# PowerGnd.net
KiCad netlist of a schematic drawn in Altium Designer
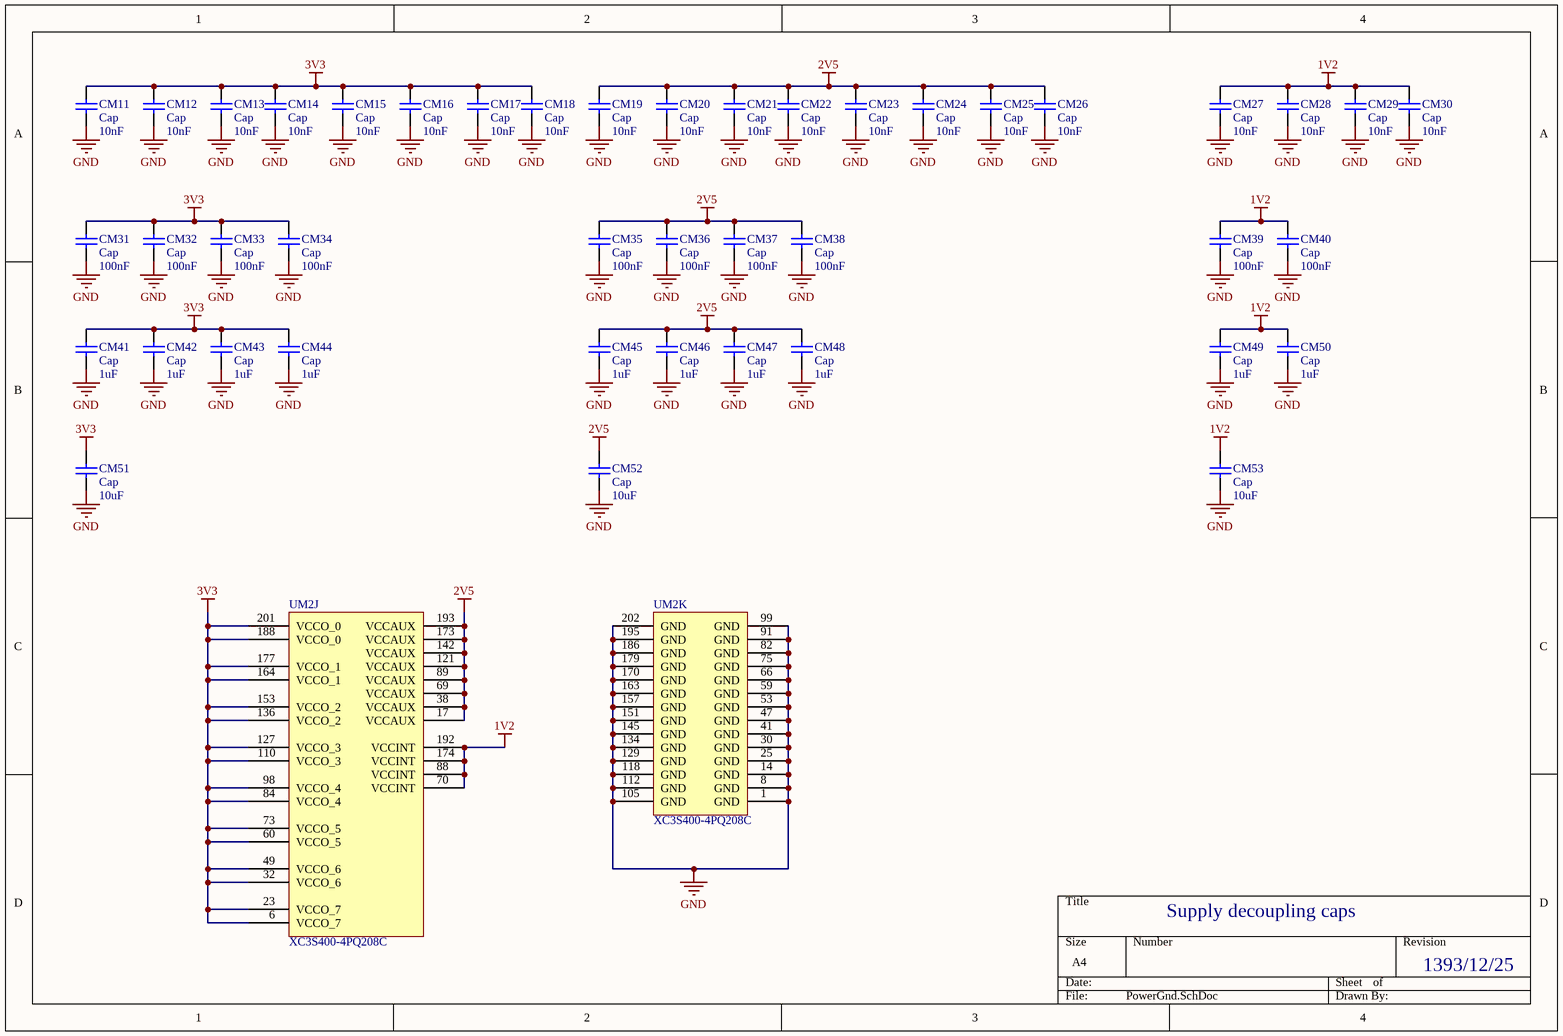
[diagram p0: PowerGnd.SchDoc]

(export (version "E")
  (design (tool "Eeschema 10.0.6"))
  (components
    (comp (ref "CM11")
      (value "Cap")
      (footprint "C0805")
      (description "Capacitor")
      (fields (field (name "ALTIUM_VALUE") "10nF") (field (name "PUBLISHER") "Altium Limited"))
      (libsource (lib "Miscellaneous Devices") (part "Cap"))
    )
    (comp (ref "CM12")
      (value "Cap")
      (footprint "C0805")
      (description "Capacitor")
      (fields (field (name "ALTIUM_VALUE") "10nF") (field (name "PUBLISHER") "Altium Limited"))
      (libsource (lib "Miscellaneous Devices") (part "Cap"))
    )
    (comp (ref "CM13")
      (value "Cap")
      (footprint "C0805")
      (description "Capacitor")
      (fields (field (name "ALTIUM_VALUE") "10nF") (field (name "PUBLISHER") "Altium Limited"))
      (libsource (lib "Miscellaneous Devices") (part "Cap"))
    )
    (comp (ref "CM14")
      (value "Cap")
      (footprint "C0805")
      (description "Capacitor")
      (fields (field (name "ALTIUM_VALUE") "10nF") (field (name "PUBLISHER") "Altium Limited"))
      (libsource (lib "Miscellaneous Devices") (part "Cap"))
    )
    (comp (ref "CM15")
      (value "Cap")
      (footprint "C0805")
      (description "Capacitor")
      (fields (field (name "ALTIUM_VALUE") "10nF") (field (name "PUBLISHER") "Altium Limited"))
      (libsource (lib "Miscellaneous Devices") (part "Cap"))
    )
    (comp (ref "CM16")
      (value "Cap")
      (footprint "C0805")
      (description "Capacitor")
      (fields (field (name "ALTIUM_VALUE") "10nF") (field (name "PUBLISHER") "Altium Limited"))
      (libsource (lib "Miscellaneous Devices") (part "Cap"))
    )
    (comp (ref "CM17")
      (value "Cap")
      (footprint "C0805")
      (description "Capacitor")
      (fields (field (name "ALTIUM_VALUE") "10nF") (field (name "PUBLISHER") "Altium Limited"))
      (libsource (lib "Miscellaneous Devices") (part "Cap"))
    )
    (comp (ref "CM18")
      (value "Cap")
      (footprint "C0805")
      (description "Capacitor")
      (fields (field (name "ALTIUM_VALUE") "10nF") (field (name "PUBLISHER") "Altium Limited"))
      (libsource (lib "Miscellaneous Devices") (part "Cap"))
    )
    (comp (ref "CM19")
      (value "Cap")
      (footprint "C0805")
      (description "Capacitor")
      (fields (field (name "ALTIUM_VALUE") "10nF") (field (name "PUBLISHER") "Altium Limited"))
      (libsource (lib "Miscellaneous Devices") (part "Cap"))
    )
    (comp (ref "CM20")
      (value "Cap")
      (footprint "C0805")
      (description "Capacitor")
      (fields (field (name "ALTIUM_VALUE") "10nF") (field (name "PUBLISHER") "Altium Limited"))
      (libsource (lib "Miscellaneous Devices") (part "Cap"))
    )
    (comp (ref "CM21")
      (value "Cap")
      (footprint "C0805")
      (description "Capacitor")
      (fields (field (name "ALTIUM_VALUE") "10nF") (field (name "PUBLISHER") "Altium Limited"))
      (libsource (lib "Miscellaneous Devices") (part "Cap"))
    )
    (comp (ref "CM22")
      (value "Cap")
      (footprint "C0805")
      (description "Capacitor")
      (fields (field (name "ALTIUM_VALUE") "10nF") (field (name "PUBLISHER") "Altium Limited"))
      (libsource (lib "Miscellaneous Devices") (part "Cap"))
    )
    (comp (ref "CM23")
      (value "Cap")
      (footprint "C0805")
      (description "Capacitor")
      (fields (field (name "ALTIUM_VALUE") "10nF") (field (name "PUBLISHER") "Altium Limited"))
      (libsource (lib "Miscellaneous Devices") (part "Cap"))
    )
    (comp (ref "CM24")
      (value "Cap")
      (footprint "C0805")
      (description "Capacitor")
      (fields (field (name "ALTIUM_VALUE") "10nF") (field (name "PUBLISHER") "Altium Limited"))
      (libsource (lib "Miscellaneous Devices") (part "Cap"))
    )
    (comp (ref "CM25")
      (value "Cap")
      (footprint "C0805")
      (description "Capacitor")
      (fields (field (name "ALTIUM_VALUE") "10nF") (field (name "PUBLISHER") "Altium Limited"))
      (libsource (lib "Miscellaneous Devices") (part "Cap"))
    )
    (comp (ref "CM26")
      (value "Cap")
      (footprint "C0805")
      (description "Capacitor")
      (fields (field (name "ALTIUM_VALUE") "10nF") (field (name "PUBLISHER") "Altium Limited"))
      (libsource (lib "Miscellaneous Devices") (part "Cap"))
    )
    (comp (ref "CM27")
      (value "Cap")
      (footprint "C0805")
      (description "Capacitor")
      (fields (field (name "ALTIUM_VALUE") "10nF") (field (name "PUBLISHER") "Altium Limited"))
      (libsource (lib "Miscellaneous Devices") (part "Cap"))
    )
    (comp (ref "CM28")
      (value "Cap")
      (footprint "C0805")
      (description "Capacitor")
      (fields (field (name "ALTIUM_VALUE") "10nF") (field (name "PUBLISHER") "Altium Limited"))
      (libsource (lib "Miscellaneous Devices") (part "Cap"))
    )
    (comp (ref "CM29")
      (value "Cap")
      (footprint "C0805")
      (description "Capacitor")
      (fields (field (name "ALTIUM_VALUE") "10nF") (field (name "PUBLISHER") "Altium Limited"))
      (libsource (lib "Miscellaneous Devices") (part "Cap"))
    )
    (comp (ref "CM30")
      (value "Cap")
      (footprint "C0805")
      (description "Capacitor")
      (fields (field (name "ALTIUM_VALUE") "10nF") (field (name "PUBLISHER") "Altium Limited"))
      (libsource (lib "Miscellaneous Devices") (part "Cap"))
    )
    (comp (ref "CM31")
      (value "Cap")
      (footprint "C0805")
      (description "Capacitor")
      (fields (field (name "ALTIUM_VALUE") "100nF") (field (name "PUBLISHER") "Altium Limited"))
      (libsource (lib "Miscellaneous Devices") (part "Cap"))
    )
    (comp (ref "CM32")
      (value "Cap")
      (footprint "C0805")
      (description "Capacitor")
      (fields (field (name "ALTIUM_VALUE") "100nF") (field (name "PUBLISHER") "Altium Limited"))
      (libsource (lib "Miscellaneous Devices") (part "Cap"))
    )
    (comp (ref "CM33")
      (value "Cap")
      (footprint "C0805")
      (description "Capacitor")
      (fields (field (name "ALTIUM_VALUE") "100nF") (field (name "PUBLISHER") "Altium Limited"))
      (libsource (lib "Miscellaneous Devices") (part "Cap"))
    )
    (comp (ref "CM34")
      (value "Cap")
      (footprint "C0805")
      (description "Capacitor")
      (fields (field (name "ALTIUM_VALUE") "100nF") (field (name "PUBLISHER") "Altium Limited"))
      (libsource (lib "Miscellaneous Devices") (part "Cap"))
    )
    (comp (ref "CM35")
      (value "Cap")
      (footprint "C0805")
      (description "Capacitor")
      (fields (field (name "ALTIUM_VALUE") "100nF") (field (name "PUBLISHER") "Altium Limited"))
      (libsource (lib "Miscellaneous Devices") (part "Cap"))
    )
    (comp (ref "CM36")
      (value "Cap")
      (footprint "C0805")
      (description "Capacitor")
      (fields (field (name "ALTIUM_VALUE") "100nF") (field (name "PUBLISHER") "Altium Limited"))
      (libsource (lib "Miscellaneous Devices") (part "Cap"))
    )
    (comp (ref "CM37")
      (value "Cap")
      (footprint "C0805")
      (description "Capacitor")
      (fields (field (name "ALTIUM_VALUE") "100nF") (field (name "PUBLISHER") "Altium Limited"))
      (libsource (lib "Miscellaneous Devices") (part "Cap"))
    )
    (comp (ref "CM38")
      (value "Cap")
      (footprint "C0805")
      (description "Capacitor")
      (fields (field (name "ALTIUM_VALUE") "100nF") (field (name "PUBLISHER") "Altium Limited"))
      (libsource (lib "Miscellaneous Devices") (part "Cap"))
    )
    (comp (ref "CM39")
      (value "Cap")
      (footprint "C0805")
      (description "Capacitor")
      (fields (field (name "ALTIUM_VALUE") "100nF") (field (name "PUBLISHER") "Altium Limited"))
      (libsource (lib "Miscellaneous Devices") (part "Cap"))
    )
    (comp (ref "CM40")
      (value "Cap")
      (footprint "C0805")
      (description "Capacitor")
      (fields (field (name "ALTIUM_VALUE") "100nF") (field (name "PUBLISHER") "Altium Limited"))
      (libsource (lib "Miscellaneous Devices") (part "Cap"))
    )
    (comp (ref "CM41")
      (value "Cap")
      (footprint "C0805")
      (description "Capacitor")
      (fields (field (name "ALTIUM_VALUE") "1uF") (field (name "PUBLISHER") "Altium Limited"))
      (libsource (lib "Miscellaneous Devices") (part "Cap"))
    )
    (comp (ref "CM42")
      (value "Cap")
      (footprint "C0805")
      (description "Capacitor")
      (fields (field (name "ALTIUM_VALUE") "1uF") (field (name "PUBLISHER") "Altium Limited"))
      (libsource (lib "Miscellaneous Devices") (part "Cap"))
    )
    (comp (ref "CM43")
      (value "Cap")
      (footprint "C0805")
      (description "Capacitor")
      (fields (field (name "ALTIUM_VALUE") "1uF") (field (name "PUBLISHER") "Altium Limited"))
      (libsource (lib "Miscellaneous Devices") (part "Cap"))
    )
    (comp (ref "CM44")
      (value "Cap")
      (footprint "C0805")
      (description "Capacitor")
      (fields (field (name "ALTIUM_VALUE") "1uF") (field (name "PUBLISHER") "Altium Limited"))
      (libsource (lib "Miscellaneous Devices") (part "Cap"))
    )
    (comp (ref "CM45")
      (value "Cap")
      (footprint "C0805")
      (description "Capacitor")
      (fields (field (name "ALTIUM_VALUE") "1uF") (field (name "PUBLISHER") "Altium Limited"))
      (libsource (lib "Miscellaneous Devices") (part "Cap"))
    )
    (comp (ref "CM46")
      (value "Cap")
      (footprint "C0805")
      (description "Capacitor")
      (fields (field (name "ALTIUM_VALUE") "1uF") (field (name "PUBLISHER") "Altium Limited"))
      (libsource (lib "Miscellaneous Devices") (part "Cap"))
    )
    (comp (ref "CM47")
      (value "Cap")
      (footprint "C0805")
      (description "Capacitor")
      (fields (field (name "ALTIUM_VALUE") "1uF") (field (name "PUBLISHER") "Altium Limited"))
      (libsource (lib "Miscellaneous Devices") (part "Cap"))
    )
    (comp (ref "CM48")
      (value "Cap")
      (footprint "C0805")
      (description "Capacitor")
      (fields (field (name "ALTIUM_VALUE") "1uF") (field (name "PUBLISHER") "Altium Limited"))
      (libsource (lib "Miscellaneous Devices") (part "Cap"))
    )
    (comp (ref "CM49")
      (value "Cap")
      (footprint "C0805")
      (description "Capacitor")
      (fields (field (name "ALTIUM_VALUE") "1uF") (field (name "PUBLISHER") "Altium Limited"))
      (libsource (lib "Miscellaneous Devices") (part "Cap"))
    )
    (comp (ref "CM50")
      (value "Cap")
      (footprint "C0805")
      (description "Capacitor")
      (fields (field (name "ALTIUM_VALUE") "1uF") (field (name "PUBLISHER") "Altium Limited"))
      (libsource (lib "Miscellaneous Devices") (part "Cap"))
    )
    (comp (ref "CM51")
      (value "Cap")
      (footprint "C0805")
      (description "Capacitor")
      (fields (field (name "ALTIUM_VALUE") "10uF") (field (name "PUBLISHER") "Altium Limited"))
      (libsource (lib "Miscellaneous Devices") (part "Cap"))
    )
    (comp (ref "CM52")
      (value "Cap")
      (footprint "C0805")
      (description "Capacitor")
      (fields (field (name "ALTIUM_VALUE") "10uF") (field (name "PUBLISHER") "Altium Limited"))
      (libsource (lib "Miscellaneous Devices") (part "Cap"))
    )
    (comp (ref "CM53")
      (value "Cap")
      (footprint "C0805")
      (description "Capacitor")
      (fields (field (name "ALTIUM_VALUE") "10uF") (field (name "PUBLISHER") "Altium Limited"))
      (libsource (lib "Miscellaneous Devices") (part "Cap"))
    )
    (comp (ref "UM2")
      (value "XC3S400-4PQ208C")
      (footprint "PQ208_N")
      (description "Spartan-3 1.2V FPGA, 141 User I/Os, 208-Pin PQFP, Standard Performance, Commercial Grade")
      (fields (field (name "PUBLISHER") "Altium Limited"))
      (libsource (lib "Xilinx Spartan-3") (part "XC3S400-4PQ208C"))
    )
  )
  (nets
    (net (code "1") (name "1V2") (class "Default")
      (node (ref "CM27") (pin "2") (pinfunction "2_2") (pintype "passive"))
      (node (ref "CM28") (pin "2") (pinfunction "2_2") (pintype "passive"))
      (node (ref "CM29") (pin "2") (pinfunction "2_2") (pintype "passive"))
      (node (ref "CM30") (pin "2") (pinfunction "2_2") (pintype "passive"))
      (node (ref "CM39") (pin "2") (pinfunction "2_2") (pintype "passive"))
      (node (ref "CM40") (pin "2") (pinfunction "2_2") (pintype "passive"))
      (node (ref "CM49") (pin "2") (pinfunction "2_2") (pintype "passive"))
      (node (ref "CM50") (pin "2") (pinfunction "2_2") (pintype "passive"))
      (node (ref "CM53") (pin "2") (pinfunction "2_2") (pintype "passive"))
      (node (ref "UM2") (pin "174") (pinfunction "VCCINT_174") (pintype "power_in"))
      (node (ref "UM2") (pin "192") (pinfunction "VCCINT_192") (pintype "power_in"))
      (node (ref "UM2") (pin "70") (pinfunction "VCCINT_70") (pintype "power_in"))
      (node (ref "UM2") (pin "88") (pinfunction "VCCINT_88") (pintype "power_in"))
    )
    (net (code "2") (name "2V5") (class "Default")
      (node (ref "CM19") (pin "2") (pinfunction "2_2") (pintype "passive"))
      (node (ref "CM20") (pin "2") (pinfunction "2_2") (pintype "passive"))
      (node (ref "CM21") (pin "2") (pinfunction "2_2") (pintype "passive"))
      (node (ref "CM22") (pin "2") (pinfunction "2_2") (pintype "passive"))
      (node (ref "CM23") (pin "2") (pinfunction "2_2") (pintype "passive"))
      (node (ref "CM24") (pin "2") (pinfunction "2_2") (pintype "passive"))
      (node (ref "CM25") (pin "2") (pinfunction "2_2") (pintype "passive"))
      (node (ref "CM26") (pin "2") (pinfunction "2_2") (pintype "passive"))
      (node (ref "CM35") (pin "2") (pinfunction "2_2") (pintype "passive"))
      (node (ref "CM36") (pin "2") (pinfunction "2_2") (pintype "passive"))
      (node (ref "CM37") (pin "2") (pinfunction "2_2") (pintype "passive"))
      (node (ref "CM38") (pin "2") (pinfunction "2_2") (pintype "passive"))
      (node (ref "CM45") (pin "2") (pinfunction "2_2") (pintype "passive"))
      (node (ref "CM46") (pin "2") (pinfunction "2_2") (pintype "passive"))
      (node (ref "CM47") (pin "2") (pinfunction "2_2") (pintype "passive"))
      (node (ref "CM48") (pin "2") (pinfunction "2_2") (pintype "passive"))
      (node (ref "CM52") (pin "2") (pinfunction "2_2") (pintype "passive"))
      (node (ref "UM2") (pin "121") (pinfunction "VCCAUX_121") (pintype "power_in"))
      (node (ref "UM2") (pin "142") (pinfunction "VCCAUX_142") (pintype "power_in"))
      (node (ref "UM2") (pin "17") (pinfunction "VCCAUX_17") (pintype "power_in"))
      (node (ref "UM2") (pin "173") (pinfunction "VCCAUX_173") (pintype "power_in"))
      (node (ref "UM2") (pin "193") (pinfunction "VCCAUX_193") (pintype "power_in"))
      (node (ref "UM2") (pin "38") (pinfunction "VCCAUX_38") (pintype "power_in"))
      (node (ref "UM2") (pin "69") (pinfunction "VCCAUX_69") (pintype "power_in"))
      (node (ref "UM2") (pin "89") (pinfunction "VCCAUX_89") (pintype "power_in"))
    )
    (net (code "3") (name "3V3") (class "Default")
      (node (ref "CM11") (pin "2") (pinfunction "2_2") (pintype "passive"))
      (node (ref "CM12") (pin "2") (pinfunction "2_2") (pintype "passive"))
      (node (ref "CM13") (pin "2") (pinfunction "2_2") (pintype "passive"))
      (node (ref "CM14") (pin "2") (pinfunction "2_2") (pintype "passive"))
      (node (ref "CM15") (pin "2") (pinfunction "2_2") (pintype "passive"))
      (node (ref "CM16") (pin "2") (pinfunction "2_2") (pintype "passive"))
      (node (ref "CM17") (pin "2") (pinfunction "2_2") (pintype "passive"))
      (node (ref "CM18") (pin "2") (pinfunction "2_2") (pintype "passive"))
      (node (ref "CM31") (pin "2") (pinfunction "2_2") (pintype "passive"))
      (node (ref "CM32") (pin "2") (pinfunction "2_2") (pintype "passive"))
      (node (ref "CM33") (pin "2") (pinfunction "2_2") (pintype "passive"))
      (node (ref "CM34") (pin "2") (pinfunction "2_2") (pintype "passive"))
      (node (ref "CM41") (pin "2") (pinfunction "2_2") (pintype "passive"))
      (node (ref "CM42") (pin "2") (pinfunction "2_2") (pintype "passive"))
      (node (ref "CM43") (pin "2") (pinfunction "2_2") (pintype "passive"))
      (node (ref "CM44") (pin "2") (pinfunction "2_2") (pintype "passive"))
      (node (ref "CM51") (pin "2") (pinfunction "2_2") (pintype "passive"))
      (node (ref "UM2") (pin "110") (pinfunction "VCCO_3_110") (pintype "power_in"))
      (node (ref "UM2") (pin "127") (pinfunction "VCCO_3_127") (pintype "power_in"))
      (node (ref "UM2") (pin "136") (pinfunction "VCCO_2_136") (pintype "power_in"))
      (node (ref "UM2") (pin "153") (pinfunction "VCCO_2_153") (pintype "power_in"))
      (node (ref "UM2") (pin "164") (pinfunction "VCCO_1_164") (pintype "power_in"))
      (node (ref "UM2") (pin "177") (pinfunction "VCCO_1_177") (pintype "power_in"))
      (node (ref "UM2") (pin "188") (pinfunction "VCCO_0_188") (pintype "power_in"))
      (node (ref "UM2") (pin "201") (pinfunction "VCCO_0_201") (pintype "power_in"))
      (node (ref "UM2") (pin "23") (pinfunction "VCCO_7_23") (pintype "power_in"))
      (node (ref "UM2") (pin "32") (pinfunction "VCCO_6_32") (pintype "power_in"))
      (node (ref "UM2") (pin "49") (pinfunction "VCCO_6_49") (pintype "power_in"))
      (node (ref "UM2") (pin "6") (pinfunction "VCCO_7_6") (pintype "power_in"))
      (node (ref "UM2") (pin "60") (pinfunction "VCCO_5_60") (pintype "power_in"))
      (node (ref "UM2") (pin "73") (pinfunction "VCCO_5_73") (pintype "power_in"))
      (node (ref "UM2") (pin "84") (pinfunction "VCCO_4_84") (pintype "power_in"))
      (node (ref "UM2") (pin "98") (pinfunction "VCCO_4_98") (pintype "power_in"))
    )
    (net (code "4") (name "GND") (class "Default")
      (node (ref "CM11") (pin "1") (pinfunction "1_1") (pintype "passive"))
      (node (ref "CM12") (pin "1") (pinfunction "1_1") (pintype "passive"))
      (node (ref "CM13") (pin "1") (pinfunction "1_1") (pintype "passive"))
      (node (ref "CM14") (pin "1") (pinfunction "1_1") (pintype "passive"))
      (node (ref "CM15") (pin "1") (pinfunction "1_1") (pintype "passive"))
      (node (ref "CM16") (pin "1") (pinfunction "1_1") (pintype "passive"))
      (node (ref "CM17") (pin "1") (pinfunction "1_1") (pintype "passive"))
      (node (ref "CM18") (pin "1") (pinfunction "1_1") (pintype "passive"))
      (node (ref "CM19") (pin "1") (pinfunction "1_1") (pintype "passive"))
      (node (ref "CM20") (pin "1") (pinfunction "1_1") (pintype "passive"))
      (node (ref "CM21") (pin "1") (pinfunction "1_1") (pintype "passive"))
      (node (ref "CM22") (pin "1") (pinfunction "1_1") (pintype "passive"))
      (node (ref "CM23") (pin "1") (pinfunction "1_1") (pintype "passive"))
      (node (ref "CM24") (pin "1") (pinfunction "1_1") (pintype "passive"))
      (node (ref "CM25") (pin "1") (pinfunction "1_1") (pintype "passive"))
      (node (ref "CM26") (pin "1") (pinfunction "1_1") (pintype "passive"))
      (node (ref "CM27") (pin "1") (pinfunction "1_1") (pintype "passive"))
      (node (ref "CM28") (pin "1") (pinfunction "1_1") (pintype "passive"))
      (node (ref "CM29") (pin "1") (pinfunction "1_1") (pintype "passive"))
      (node (ref "CM30") (pin "1") (pinfunction "1_1") (pintype "passive"))
      (node (ref "CM31") (pin "1") (pinfunction "1_1") (pintype "passive"))
      (node (ref "CM32") (pin "1") (pinfunction "1_1") (pintype "passive"))
      (node (ref "CM33") (pin "1") (pinfunction "1_1") (pintype "passive"))
      (node (ref "CM34") (pin "1") (pinfunction "1_1") (pintype "passive"))
      (node (ref "CM35") (pin "1") (pinfunction "1_1") (pintype "passive"))
      (node (ref "CM36") (pin "1") (pinfunction "1_1") (pintype "passive"))
      (node (ref "CM37") (pin "1") (pinfunction "1_1") (pintype "passive"))
      (node (ref "CM38") (pin "1") (pinfunction "1_1") (pintype "passive"))
      (node (ref "CM39") (pin "1") (pinfunction "1_1") (pintype "passive"))
      (node (ref "CM40") (pin "1") (pinfunction "1_1") (pintype "passive"))
      (node (ref "CM41") (pin "1") (pinfunction "1_1") (pintype "passive"))
      (node (ref "CM42") (pin "1") (pinfunction "1_1") (pintype "passive"))
      (node (ref "CM43") (pin "1") (pinfunction "1_1") (pintype "passive"))
      (node (ref "CM44") (pin "1") (pinfunction "1_1") (pintype "passive"))
      (node (ref "CM45") (pin "1") (pinfunction "1_1") (pintype "passive"))
      (node (ref "CM46") (pin "1") (pinfunction "1_1") (pintype "passive"))
      (node (ref "CM47") (pin "1") (pinfunction "1_1") (pintype "passive"))
      (node (ref "CM48") (pin "1") (pinfunction "1_1") (pintype "passive"))
      (node (ref "CM49") (pin "1") (pinfunction "1_1") (pintype "passive"))
      (node (ref "CM50") (pin "1") (pinfunction "1_1") (pintype "passive"))
      (node (ref "CM51") (pin "1") (pinfunction "1_1") (pintype "passive"))
      (node (ref "CM52") (pin "1") (pinfunction "1_1") (pintype "passive"))
      (node (ref "CM53") (pin "1") (pinfunction "1_1") (pintype "passive"))
      (node (ref "UM2") (pin "1") (pinfunction "GND_1") (pintype "power_in"))
      (node (ref "UM2") (pin "105") (pinfunction "GND_105") (pintype "power_in"))
      (node (ref "UM2") (pin "112") (pinfunction "GND_112") (pintype "power_in"))
      (node (ref "UM2") (pin "118") (pinfunction "GND_118") (pintype "power_in"))
      (node (ref "UM2") (pin "129") (pinfunction "GND_129") (pintype "power_in"))
      (node (ref "UM2") (pin "134") (pinfunction "GND_134") (pintype "power_in"))
      (node (ref "UM2") (pin "14") (pinfunction "GND_14") (pintype "power_in"))
      (node (ref "UM2") (pin "145") (pinfunction "GND_145") (pintype "power_in"))
      (node (ref "UM2") (pin "151") (pinfunction "GND_151") (pintype "power_in"))
      (node (ref "UM2") (pin "157") (pinfunction "GND_157") (pintype "power_in"))
      (node (ref "UM2") (pin "163") (pinfunction "GND_163") (pintype "power_in"))
      (node (ref "UM2") (pin "170") (pinfunction "GND_170") (pintype "power_in"))
      (node (ref "UM2") (pin "179") (pinfunction "GND_179") (pintype "power_in"))
      (node (ref "UM2") (pin "186") (pinfunction "GND_186") (pintype "power_in"))
      (node (ref "UM2") (pin "195") (pinfunction "GND_195") (pintype "power_in"))
      (node (ref "UM2") (pin "202") (pinfunction "GND_202") (pintype "power_in"))
      (node (ref "UM2") (pin "25") (pinfunction "GND_25") (pintype "power_in"))
      (node (ref "UM2") (pin "30") (pinfunction "GND_30") (pintype "power_in"))
      (node (ref "UM2") (pin "41") (pinfunction "GND_41") (pintype "power_in"))
      (node (ref "UM2") (pin "47") (pinfunction "GND_47") (pintype "power_in"))
      (node (ref "UM2") (pin "53") (pinfunction "GND_53") (pintype "power_in"))
      (node (ref "UM2") (pin "59") (pinfunction "GND_59") (pintype "power_in"))
      (node (ref "UM2") (pin "66") (pinfunction "GND_66") (pintype "power_in"))
      (node (ref "UM2") (pin "75") (pinfunction "GND_75") (pintype "power_in"))
      (node (ref "UM2") (pin "8") (pinfunction "GND_8") (pintype "power_in"))
      (node (ref "UM2") (pin "82") (pinfunction "GND_82") (pintype "power_in"))
      (node (ref "UM2") (pin "91") (pinfunction "GND_91") (pintype "power_in"))
      (node (ref "UM2") (pin "99") (pinfunction "GND_99") (pintype "power_in"))
    )
  )
)
